# rectifiers.net
KiCad netlist of a schematic drawn in Altium Designer
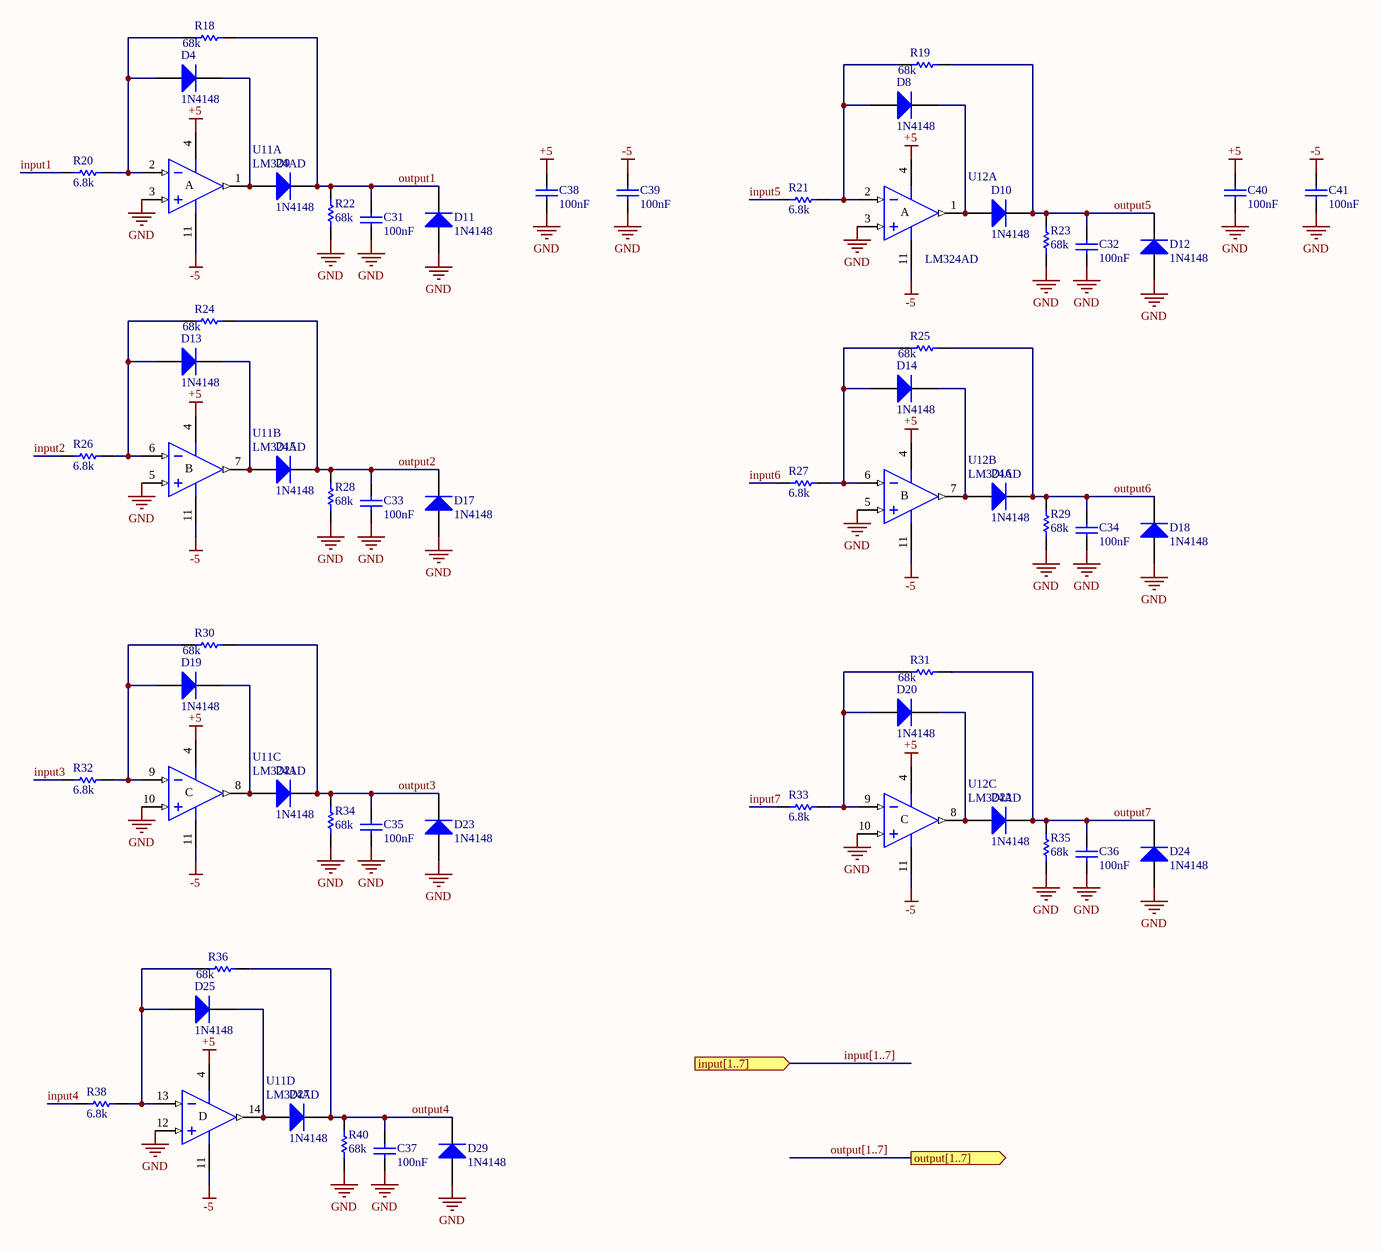
[diagram p0: rectifiers.SchDoc]

(export (version "E")
  (design (tool "Eeschema 10.0.6"))
  (components
    (comp (ref "C31")
      (value "100nF")
      (footprint "SMD_CAP_0805")
      (description "CAP-100Nf")
      (fields (field (name "Comment") "Cap"))
      (libsource (lib "Altium library (www.AVRelec.com)") (part "Cap ceramic"))
    )
    (comp (ref "C32")
      (value "100nF")
      (footprint "SMD_CAP_0805")
      (description "CAP-100Nf")
      (fields (field (name "Comment") "Cap"))
      (libsource (lib "Altium library (www.AVRelec.com)") (part "Cap ceramic"))
    )
    (comp (ref "C33")
      (value "100nF")
      (footprint "SMD_CAP_0805")
      (description "CAP-100Nf")
      (fields (field (name "Comment") "Cap"))
      (libsource (lib "Altium library (www.AVRelec.com)") (part "Cap ceramic"))
    )
    (comp (ref "C34")
      (value "100nF")
      (footprint "SMD_CAP_0805")
      (description "CAP-100Nf")
      (fields (field (name "Comment") "Cap"))
      (libsource (lib "Altium library (www.AVRelec.com)") (part "Cap ceramic"))
    )
    (comp (ref "C35")
      (value "100nF")
      (footprint "SMD_CAP_0805")
      (description "CAP-100Nf")
      (fields (field (name "Comment") "Cap"))
      (libsource (lib "Altium library (www.AVRelec.com)") (part "Cap ceramic"))
    )
    (comp (ref "C36")
      (value "100nF")
      (footprint "SMD_CAP_0805")
      (description "CAP-100Nf")
      (fields (field (name "Comment") "Cap"))
      (libsource (lib "Altium library (www.AVRelec.com)") (part "Cap ceramic"))
    )
    (comp (ref "C37")
      (value "100nF")
      (footprint "SMD_CAP_0805")
      (description "CAP-100Nf")
      (fields (field (name "Comment") "Cap"))
      (libsource (lib "Altium library (www.AVRelec.com)") (part "Cap ceramic"))
    )
    (comp (ref "C38")
      (value "100nF")
      (footprint "SMD_CAP_0805")
      (description "CAP-100Nf")
      (fields (field (name "Comment") "Cap"))
      (libsource (lib "Altium library (www.AVRelec.com)") (part "Cap ceramic"))
    )
    (comp (ref "C39")
      (value "100nF")
      (footprint "SMD_CAP_0805")
      (description "CAP-100Nf")
      (fields (field (name "Comment") "Cap"))
      (libsource (lib "Altium library (www.AVRelec.com)") (part "Cap ceramic"))
    )
    (comp (ref "C40")
      (value "100nF")
      (footprint "SMD_CAP_0805")
      (description "CAP-100Nf")
      (fields (field (name "Comment") "Cap"))
      (libsource (lib "Altium library (www.AVRelec.com)") (part "Cap ceramic"))
    )
    (comp (ref "C41")
      (value "100nF")
      (footprint "SMD_CAP_0805")
      (description "CAP-100Nf")
      (fields (field (name "Comment") "Cap"))
      (libsource (lib "Altium library (www.AVRelec.com)") (part "Cap ceramic"))
    )
    (comp (ref "D4")
      (value "1N4148")
      (footprint "LL4148")
      (description "High Conductance Fast Diode")
      (fields (field (name "PUBLISHER") "Altium Limited"))
      (libsource (lib "Miscellaneous Devices") (part "Diode 1N4148"))
    )
    (comp (ref "D8")
      (value "1N4148")
      (footprint "LL4148")
      (description "High Conductance Fast Diode")
      (fields (field (name "PUBLISHER") "Altium Limited"))
      (libsource (lib "Miscellaneous Devices") (part "Diode 1N4148"))
    )
    (comp (ref "D9")
      (value "1N4148")
      (footprint "LL4148")
      (description "High Conductance Fast Diode")
      (fields (field (name "PUBLISHER") "Altium Limited"))
      (libsource (lib "Miscellaneous Devices") (part "Diode 1N4148"))
    )
    (comp (ref "D10")
      (value "1N4148")
      (footprint "LL4148")
      (description "High Conductance Fast Diode")
      (fields (field (name "PUBLISHER") "Altium Limited"))
      (libsource (lib "Miscellaneous Devices") (part "Diode 1N4148"))
    )
    (comp (ref "D11")
      (value "1N4148")
      (footprint "LL4148")
      (description "High Conductance Fast Diode")
      (fields (field (name "PUBLISHER") "Altium Limited"))
      (libsource (lib "Miscellaneous Devices") (part "Diode 1N4148"))
    )
    (comp (ref "D12")
      (value "1N4148")
      (footprint "LL4148")
      (description "High Conductance Fast Diode")
      (fields (field (name "PUBLISHER") "Altium Limited"))
      (libsource (lib "Miscellaneous Devices") (part "Diode 1N4148"))
    )
    (comp (ref "D13")
      (value "1N4148")
      (footprint "LL4148")
      (description "High Conductance Fast Diode")
      (fields (field (name "PUBLISHER") "Altium Limited"))
      (libsource (lib "Miscellaneous Devices") (part "Diode 1N4148"))
    )
    (comp (ref "D14")
      (value "1N4148")
      (footprint "LL4148")
      (description "High Conductance Fast Diode")
      (fields (field (name "PUBLISHER") "Altium Limited"))
      (libsource (lib "Miscellaneous Devices") (part "Diode 1N4148"))
    )
    (comp (ref "D15")
      (value "1N4148")
      (footprint "LL4148")
      (description "High Conductance Fast Diode")
      (fields (field (name "PUBLISHER") "Altium Limited"))
      (libsource (lib "Miscellaneous Devices") (part "Diode 1N4148"))
    )
    (comp (ref "D16")
      (value "1N4148")
      (footprint "LL4148")
      (description "High Conductance Fast Diode")
      (fields (field (name "PUBLISHER") "Altium Limited"))
      (libsource (lib "Miscellaneous Devices") (part "Diode 1N4148"))
    )
    (comp (ref "D17")
      (value "1N4148")
      (footprint "LL4148")
      (description "High Conductance Fast Diode")
      (fields (field (name "PUBLISHER") "Altium Limited"))
      (libsource (lib "Miscellaneous Devices") (part "Diode 1N4148"))
    )
    (comp (ref "D18")
      (value "1N4148")
      (footprint "LL4148")
      (description "High Conductance Fast Diode")
      (fields (field (name "PUBLISHER") "Altium Limited"))
      (libsource (lib "Miscellaneous Devices") (part "Diode 1N4148"))
    )
    (comp (ref "D19")
      (value "1N4148")
      (footprint "LL4148")
      (description "High Conductance Fast Diode")
      (fields (field (name "PUBLISHER") "Altium Limited"))
      (libsource (lib "Miscellaneous Devices") (part "Diode 1N4148"))
    )
    (comp (ref "D20")
      (value "1N4148")
      (footprint "LL4148")
      (description "High Conductance Fast Diode")
      (fields (field (name "PUBLISHER") "Altium Limited"))
      (libsource (lib "Miscellaneous Devices") (part "Diode 1N4148"))
    )
    (comp (ref "D21")
      (value "1N4148")
      (footprint "LL4148")
      (description "High Conductance Fast Diode")
      (fields (field (name "PUBLISHER") "Altium Limited"))
      (libsource (lib "Miscellaneous Devices") (part "Diode 1N4148"))
    )
    (comp (ref "D22")
      (value "1N4148")
      (footprint "LL4148")
      (description "High Conductance Fast Diode")
      (fields (field (name "PUBLISHER") "Altium Limited"))
      (libsource (lib "Miscellaneous Devices") (part "Diode 1N4148"))
    )
    (comp (ref "D23")
      (value "1N4148")
      (footprint "LL4148")
      (description "High Conductance Fast Diode")
      (fields (field (name "PUBLISHER") "Altium Limited"))
      (libsource (lib "Miscellaneous Devices") (part "Diode 1N4148"))
    )
    (comp (ref "D24")
      (value "1N4148")
      (footprint "LL4148")
      (description "High Conductance Fast Diode")
      (fields (field (name "PUBLISHER") "Altium Limited"))
      (libsource (lib "Miscellaneous Devices") (part "Diode 1N4148"))
    )
    (comp (ref "D25")
      (value "1N4148")
      (footprint "LL4148")
      (description "High Conductance Fast Diode")
      (fields (field (name "PUBLISHER") "Altium Limited"))
      (libsource (lib "Miscellaneous Devices") (part "Diode 1N4148"))
    )
    (comp (ref "D27")
      (value "1N4148")
      (footprint "LL4148")
      (description "High Conductance Fast Diode")
      (fields (field (name "PUBLISHER") "Altium Limited"))
      (libsource (lib "Miscellaneous Devices") (part "Diode 1N4148"))
    )
    (comp (ref "D29")
      (value "1N4148")
      (footprint "LL4148")
      (description "High Conductance Fast Diode")
      (fields (field (name "PUBLISHER") "Altium Limited"))
      (libsource (lib "Miscellaneous Devices") (part "Diode 1N4148"))
    )
    (comp (ref "R18")
      (value "68k")
      (footprint "RES 0805 (2012X06L)")
      (description "Resistor")
      (fields (field (name "Comment") "Res1") (field (name "PUBLISHER") "Altium Limited"))
      (libsource (lib "Miscellaneous Devices") (part "Res1"))
    )
    (comp (ref "R19")
      (value "68k")
      (footprint "RES 0805 (2012X06L)")
      (description "Resistor")
      (fields (field (name "Comment") "Res1") (field (name "PUBLISHER") "Altium Limited"))
      (libsource (lib "Miscellaneous Devices") (part "Res1"))
    )
    (comp (ref "R20")
      (value "6.8k")
      (footprint "RES 0805 (2012X06L)")
      (description "Resistor")
      (fields (field (name "Comment") "Res1") (field (name "PUBLISHER") "Altium Limited"))
      (libsource (lib "Miscellaneous Devices") (part "Res1"))
    )
    (comp (ref "R21")
      (value "6.8k")
      (footprint "RES 0805 (2012X06L)")
      (description "Resistor")
      (fields (field (name "Comment") "Res1") (field (name "PUBLISHER") "Altium Limited"))
      (libsource (lib "Miscellaneous Devices") (part "Res1"))
    )
    (comp (ref "R22")
      (value "68k")
      (footprint "RES 0805 (2012X06L)")
      (description "Resistor")
      (fields (field (name "Comment") "Res1") (field (name "PUBLISHER") "Altium Limited"))
      (libsource (lib "Miscellaneous Devices") (part "Res1"))
    )
    (comp (ref "R23")
      (value "68k")
      (footprint "RES 0805 (2012X06L)")
      (description "Resistor")
      (fields (field (name "Comment") "Res1") (field (name "PUBLISHER") "Altium Limited"))
      (libsource (lib "Miscellaneous Devices") (part "Res1"))
    )
    (comp (ref "R24")
      (value "68k")
      (footprint "RES 0805 (2012X06L)")
      (description "Resistor")
      (fields (field (name "Comment") "Res1") (field (name "PUBLISHER") "Altium Limited"))
      (libsource (lib "Miscellaneous Devices") (part "Res1"))
    )
    (comp (ref "R25")
      (value "68k")
      (footprint "RES 0805 (2012X06L)")
      (description "Resistor")
      (fields (field (name "Comment") "Res1") (field (name "PUBLISHER") "Altium Limited"))
      (libsource (lib "Miscellaneous Devices") (part "Res1"))
    )
    (comp (ref "R26")
      (value "6.8k")
      (footprint "RES 0805 (2012X06L)")
      (description "Resistor")
      (fields (field (name "Comment") "Res1") (field (name "PUBLISHER") "Altium Limited"))
      (libsource (lib "Miscellaneous Devices") (part "Res1"))
    )
    (comp (ref "R27")
      (value "6.8k")
      (footprint "RES 0805 (2012X06L)")
      (description "Resistor")
      (fields (field (name "Comment") "Res1") (field (name "PUBLISHER") "Altium Limited"))
      (libsource (lib "Miscellaneous Devices") (part "Res1"))
    )
    (comp (ref "R28")
      (value "68k")
      (footprint "RES 0805 (2012X06L)")
      (description "Resistor")
      (fields (field (name "Comment") "Res1") (field (name "PUBLISHER") "Altium Limited"))
      (libsource (lib "Miscellaneous Devices") (part "Res1"))
    )
    (comp (ref "R29")
      (value "68k")
      (footprint "RES 0805 (2012X06L)")
      (description "Resistor")
      (fields (field (name "Comment") "Res1") (field (name "PUBLISHER") "Altium Limited"))
      (libsource (lib "Miscellaneous Devices") (part "Res1"))
    )
    (comp (ref "R30")
      (value "68k")
      (footprint "RES 0805 (2012X06L)")
      (description "Resistor")
      (fields (field (name "Comment") "Res1") (field (name "PUBLISHER") "Altium Limited"))
      (libsource (lib "Miscellaneous Devices") (part "Res1"))
    )
    (comp (ref "R31")
      (value "68k")
      (footprint "RES 0805 (2012X06L)")
      (description "Resistor")
      (fields (field (name "Comment") "Res1") (field (name "PUBLISHER") "Altium Limited"))
      (libsource (lib "Miscellaneous Devices") (part "Res1"))
    )
    (comp (ref "R32")
      (value "6.8k")
      (footprint "RES 0805 (2012X06L)")
      (description "Resistor")
      (fields (field (name "Comment") "Res1") (field (name "PUBLISHER") "Altium Limited"))
      (libsource (lib "Miscellaneous Devices") (part "Res1"))
    )
    (comp (ref "R33")
      (value "6.8k")
      (footprint "RES 0805 (2012X06L)")
      (description "Resistor")
      (fields (field (name "Comment") "Res1") (field (name "PUBLISHER") "Altium Limited"))
      (libsource (lib "Miscellaneous Devices") (part "Res1"))
    )
    (comp (ref "R34")
      (value "68k")
      (footprint "RES 0805 (2012X06L)")
      (description "Resistor")
      (fields (field (name "Comment") "Res1") (field (name "PUBLISHER") "Altium Limited"))
      (libsource (lib "Miscellaneous Devices") (part "Res1"))
    )
    (comp (ref "R35")
      (value "68k")
      (footprint "RES 0805 (2012X06L)")
      (description "Resistor")
      (fields (field (name "Comment") "Res1") (field (name "PUBLISHER") "Altium Limited"))
      (libsource (lib "Miscellaneous Devices") (part "Res1"))
    )
    (comp (ref "R36")
      (value "68k")
      (footprint "RES 0805 (2012X06L)")
      (description "Resistor")
      (fields (field (name "Comment") "Res1") (field (name "PUBLISHER") "Altium Limited"))
      (libsource (lib "Miscellaneous Devices") (part "Res1"))
    )
    (comp (ref "R38")
      (value "6.8k")
      (footprint "RES 0805 (2012X06L)")
      (description "Resistor")
      (fields (field (name "Comment") "Res1") (field (name "PUBLISHER") "Altium Limited"))
      (libsource (lib "Miscellaneous Devices") (part "Res1"))
    )
    (comp (ref "R40")
      (value "68k")
      (footprint "RES 0805 (2012X06L)")
      (description "Resistor")
      (fields (field (name "Comment") "Res1") (field (name "PUBLISHER") "Altium Limited"))
      (libsource (lib "Miscellaneous Devices") (part "Res1"))
    )
    (comp (ref "U11")
      (value "LM324AD")
      (footprint "SO14_N")
      (description "Low-Power Quad Operational Amplifier")
      (fields (field (name "PUBLISHER") "Altium Limited"))
      (libsource (lib "ST Operational Amplifier") (part "LM324AD"))
    )
    (comp (ref "U12")
      (value "LM324AD")
      (footprint "SO14_N")
      (description "Low-Power Quad Operational Amplifier")
      (fields (field (name "PUBLISHER") "Altium Limited"))
      (libsource (lib "ST Operational Amplifier") (part "LM324AD"))
    )
  )
  (nets
    (net (code "1") (name "+5") (class "Default")
      (node (ref "C38") (pin "2") (pinfunction "2_2") (pintype "passive"))
      (node (ref "C40") (pin "2") (pinfunction "2_2") (pintype "passive"))
      (node (ref "U11") (pin "4") (pinfunction "V+_4") (pintype "power_in"))
      (node (ref "U12") (pin "4") (pinfunction "V+_4") (pintype "power_in"))
    )
    (net (code "2") (name "-5") (class "Default")
      (node (ref "C39") (pin "2") (pinfunction "2_2") (pintype "passive"))
      (node (ref "C41") (pin "2") (pinfunction "2_2") (pintype "passive"))
      (node (ref "U11") (pin "11") (pinfunction "V-_11") (pintype "power_in"))
      (node (ref "U12") (pin "11") (pinfunction "V-_11") (pintype "power_in"))
    )
    (net (code "3") (name "/input1") (class "Default")
      (node (ref "R20") (pin "1") (pinfunction "1_1") (pintype "passive"))
    )
    (net (code "4") (name "/input2") (class "Default")
      (node (ref "R26") (pin "1") (pinfunction "1_1") (pintype "passive"))
    )
    (net (code "5") (name "/input3") (class "Default")
      (node (ref "R32") (pin "1") (pinfunction "1_1") (pintype "passive"))
    )
    (net (code "6") (name "/input4") (class "Default")
      (node (ref "R38") (pin "1") (pinfunction "1_1") (pintype "passive"))
    )
    (net (code "7") (name "/input5") (class "Default")
      (node (ref "R21") (pin "1") (pinfunction "1_1") (pintype "passive"))
    )
    (net (code "8") (name "/input6") (class "Default")
      (node (ref "R27") (pin "1") (pinfunction "1_1") (pintype "passive"))
    )
    (net (code "9") (name "/input7") (class "Default")
      (node (ref "R33") (pin "1") (pinfunction "1_1") (pintype "passive"))
    )
    (net (code "11") (name "/output1") (class "Default")
      (node (ref "C31") (pin "2") (pinfunction "2_2") (pintype "passive"))
      (node (ref "D11") (pin "2") (pinfunction "K_2") (pintype "passive"))
      (node (ref "D9") (pin "2") (pinfunction "K_2") (pintype "passive"))
      (node (ref "R18") (pin "2") (pinfunction "2_2") (pintype "passive"))
      (node (ref "R22") (pin "2") (pinfunction "2_2") (pintype "passive"))
    )
    (net (code "12") (name "/output2") (class "Default")
      (node (ref "C33") (pin "2") (pinfunction "2_2") (pintype "passive"))
      (node (ref "D15") (pin "2") (pinfunction "K_2") (pintype "passive"))
      (node (ref "D17") (pin "2") (pinfunction "K_2") (pintype "passive"))
      (node (ref "R24") (pin "2") (pinfunction "2_2") (pintype "passive"))
      (node (ref "R28") (pin "2") (pinfunction "2_2") (pintype "passive"))
    )
    (net (code "13") (name "/output3") (class "Default")
      (node (ref "C35") (pin "2") (pinfunction "2_2") (pintype "passive"))
      (node (ref "D21") (pin "2") (pinfunction "K_2") (pintype "passive"))
      (node (ref "D23") (pin "2") (pinfunction "K_2") (pintype "passive"))
      (node (ref "R30") (pin "2") (pinfunction "2_2") (pintype "passive"))
      (node (ref "R34") (pin "2") (pinfunction "2_2") (pintype "passive"))
    )
    (net (code "14") (name "/output4") (class "Default")
      (node (ref "C37") (pin "2") (pinfunction "2_2") (pintype "passive"))
      (node (ref "D27") (pin "2") (pinfunction "K_2") (pintype "passive"))
      (node (ref "D29") (pin "2") (pinfunction "K_2") (pintype "passive"))
      (node (ref "R36") (pin "2") (pinfunction "2_2") (pintype "passive"))
      (node (ref "R40") (pin "2") (pinfunction "2_2") (pintype "passive"))
    )
    (net (code "15") (name "/output5") (class "Default")
      (node (ref "C32") (pin "2") (pinfunction "2_2") (pintype "passive"))
      (node (ref "D10") (pin "2") (pinfunction "K_2") (pintype "passive"))
      (node (ref "D12") (pin "2") (pinfunction "K_2") (pintype "passive"))
      (node (ref "R19") (pin "2") (pinfunction "2_2") (pintype "passive"))
      (node (ref "R23") (pin "2") (pinfunction "2_2") (pintype "passive"))
    )
    (net (code "16") (name "/output6") (class "Default")
      (node (ref "C34") (pin "2") (pinfunction "2_2") (pintype "passive"))
      (node (ref "D16") (pin "2") (pinfunction "K_2") (pintype "passive"))
      (node (ref "D18") (pin "2") (pinfunction "K_2") (pintype "passive"))
      (node (ref "R25") (pin "2") (pinfunction "2_2") (pintype "passive"))
      (node (ref "R29") (pin "2") (pinfunction "2_2") (pintype "passive"))
    )
    (net (code "17") (name "/output7") (class "Default")
      (node (ref "C36") (pin "2") (pinfunction "2_2") (pintype "passive"))
      (node (ref "D22") (pin "2") (pinfunction "K_2") (pintype "passive"))
      (node (ref "D24") (pin "2") (pinfunction "K_2") (pintype "passive"))
      (node (ref "R31") (pin "2") (pinfunction "2_2") (pintype "passive"))
      (node (ref "R35") (pin "2") (pinfunction "2_2") (pintype "passive"))
    )
    (net (code "19") (name "GND") (class "Default")
      (node (ref "C31") (pin "1") (pinfunction "1_1") (pintype "passive"))
      (node (ref "C32") (pin "1") (pinfunction "1_1") (pintype "passive"))
      (node (ref "C33") (pin "1") (pinfunction "1_1") (pintype "passive"))
      (node (ref "C34") (pin "1") (pinfunction "1_1") (pintype "passive"))
      (node (ref "C35") (pin "1") (pinfunction "1_1") (pintype "passive"))
      (node (ref "C36") (pin "1") (pinfunction "1_1") (pintype "passive"))
      (node (ref "C37") (pin "1") (pinfunction "1_1") (pintype "passive"))
      (node (ref "C38") (pin "1") (pinfunction "1_1") (pintype "passive"))
      (node (ref "C39") (pin "1") (pinfunction "1_1") (pintype "passive"))
      (node (ref "C40") (pin "1") (pinfunction "1_1") (pintype "passive"))
      (node (ref "C41") (pin "1") (pinfunction "1_1") (pintype "passive"))
      (node (ref "D11") (pin "1") (pinfunction "A_1") (pintype "passive"))
      (node (ref "D12") (pin "1") (pinfunction "A_1") (pintype "passive"))
      (node (ref "D17") (pin "1") (pinfunction "A_1") (pintype "passive"))
      (node (ref "D18") (pin "1") (pinfunction "A_1") (pintype "passive"))
      (node (ref "D23") (pin "1") (pinfunction "A_1") (pintype "passive"))
      (node (ref "D24") (pin "1") (pinfunction "A_1") (pintype "passive"))
      (node (ref "D29") (pin "1") (pinfunction "A_1") (pintype "passive"))
      (node (ref "R22") (pin "1") (pinfunction "1_1") (pintype "passive"))
      (node (ref "R23") (pin "1") (pinfunction "1_1") (pintype "passive"))
      (node (ref "R28") (pin "1") (pinfunction "1_1") (pintype "passive"))
      (node (ref "R29") (pin "1") (pinfunction "1_1") (pintype "passive"))
      (node (ref "R34") (pin "1") (pinfunction "1_1") (pintype "passive"))
      (node (ref "R35") (pin "1") (pinfunction "1_1") (pintype "passive"))
      (node (ref "R40") (pin "1") (pinfunction "1_1") (pintype "passive"))
      (node (ref "U11") (pin "10") (pinfunction "IN+_10") (pintype "input"))
      (node (ref "U11") (pin "12") (pinfunction "IN+_12") (pintype "input"))
      (node (ref "U11") (pin "3") (pinfunction "IN+_3") (pintype "input"))
      (node (ref "U11") (pin "5") (pinfunction "IN+_5") (pintype "input"))
      (node (ref "U12") (pin "10") (pinfunction "IN+_10") (pintype "input"))
      (node (ref "U12") (pin "3") (pinfunction "IN+_3") (pintype "input"))
      (node (ref "U12") (pin "5") (pinfunction "IN+_5") (pintype "input"))
    )
    (net (code "20") (name "Net-(D4-A)") (class "Default")
      (node (ref "D4") (pin "1") (pinfunction "A_1") (pintype "passive"))
      (node (ref "R18") (pin "1") (pinfunction "1_1") (pintype "passive"))
      (node (ref "R20") (pin "2") (pinfunction "2_2") (pintype "passive"))
      (node (ref "U11") (pin "2") (pinfunction "IN-_2") (pintype "input"))
    )
    (net (code "21") (name "Net-(D4-K)") (class "Default")
      (node (ref "D4") (pin "2") (pinfunction "K_2") (pintype "passive"))
      (node (ref "D9") (pin "1") (pinfunction "A_1") (pintype "passive"))
      (node (ref "U11") (pin "1") (pinfunction "OUT_1") (pintype "output"))
    )
    (net (code "22") (name "Net-(D8-A)") (class "Default")
      (node (ref "D8") (pin "1") (pinfunction "A_1") (pintype "passive"))
      (node (ref "R19") (pin "1") (pinfunction "1_1") (pintype "passive"))
      (node (ref "R21") (pin "2") (pinfunction "2_2") (pintype "passive"))
      (node (ref "U12") (pin "2") (pinfunction "IN-_2") (pintype "input"))
    )
    (net (code "23") (name "Net-(D10-A)") (class "Default")
      (node (ref "D10") (pin "1") (pinfunction "A_1") (pintype "passive"))
      (node (ref "D8") (pin "2") (pinfunction "K_2") (pintype "passive"))
      (node (ref "U12") (pin "1") (pinfunction "OUT_1") (pintype "output"))
    )
    (net (code "24") (name "Net-(D13-A)") (class "Default")
      (node (ref "D13") (pin "1") (pinfunction "A_1") (pintype "passive"))
      (node (ref "R24") (pin "1") (pinfunction "1_1") (pintype "passive"))
      (node (ref "R26") (pin "2") (pinfunction "2_2") (pintype "passive"))
      (node (ref "U11") (pin "6") (pinfunction "IN-_6") (pintype "input"))
    )
    (net (code "25") (name "Net-(D13-K)") (class "Default")
      (node (ref "D13") (pin "2") (pinfunction "K_2") (pintype "passive"))
      (node (ref "D15") (pin "1") (pinfunction "A_1") (pintype "passive"))
      (node (ref "U11") (pin "7") (pinfunction "OUT_7") (pintype "output"))
    )
    (net (code "26") (name "Net-(D14-A)") (class "Default")
      (node (ref "D14") (pin "1") (pinfunction "A_1") (pintype "passive"))
      (node (ref "R25") (pin "1") (pinfunction "1_1") (pintype "passive"))
      (node (ref "R27") (pin "2") (pinfunction "2_2") (pintype "passive"))
      (node (ref "U12") (pin "6") (pinfunction "IN-_6") (pintype "input"))
    )
    (net (code "27") (name "Net-(D14-K)") (class "Default")
      (node (ref "D14") (pin "2") (pinfunction "K_2") (pintype "passive"))
      (node (ref "D16") (pin "1") (pinfunction "A_1") (pintype "passive"))
      (node (ref "U12") (pin "7") (pinfunction "OUT_7") (pintype "output"))
    )
    (net (code "28") (name "Net-(D19-A)") (class "Default")
      (node (ref "D19") (pin "1") (pinfunction "A_1") (pintype "passive"))
      (node (ref "R30") (pin "1") (pinfunction "1_1") (pintype "passive"))
      (node (ref "R32") (pin "2") (pinfunction "2_2") (pintype "passive"))
      (node (ref "U11") (pin "9") (pinfunction "IN-_9") (pintype "input"))
    )
    (net (code "29") (name "Net-(D19-K)") (class "Default")
      (node (ref "D19") (pin "2") (pinfunction "K_2") (pintype "passive"))
      (node (ref "D21") (pin "1") (pinfunction "A_1") (pintype "passive"))
      (node (ref "U11") (pin "8") (pinfunction "OUT_8") (pintype "output"))
    )
    (net (code "30") (name "Net-(D20-A)") (class "Default")
      (node (ref "D20") (pin "1") (pinfunction "A_1") (pintype "passive"))
      (node (ref "R31") (pin "1") (pinfunction "1_1") (pintype "passive"))
      (node (ref "R33") (pin "2") (pinfunction "2_2") (pintype "passive"))
      (node (ref "U12") (pin "9") (pinfunction "IN-_9") (pintype "input"))
    )
    (net (code "31") (name "Net-(D20-K)") (class "Default")
      (node (ref "D20") (pin "2") (pinfunction "K_2") (pintype "passive"))
      (node (ref "D22") (pin "1") (pinfunction "A_1") (pintype "passive"))
      (node (ref "U12") (pin "8") (pinfunction "OUT_8") (pintype "output"))
    )
    (net (code "32") (name "Net-(D25-A)") (class "Default")
      (node (ref "D25") (pin "1") (pinfunction "A_1") (pintype "passive"))
      (node (ref "R36") (pin "1") (pinfunction "1_1") (pintype "passive"))
      (node (ref "R38") (pin "2") (pinfunction "2_2") (pintype "passive"))
      (node (ref "U11") (pin "13") (pinfunction "IN-_13") (pintype "input"))
    )
    (net (code "33") (name "Net-(D25-K)") (class "Default")
      (node (ref "D25") (pin "2") (pinfunction "K_2") (pintype "passive"))
      (node (ref "D27") (pin "1") (pinfunction "A_1") (pintype "passive"))
      (node (ref "U11") (pin "14") (pinfunction "OUT_14") (pintype "output"))
    )
  )
)
